# eth.net
KiCad netlist of a schematic drawn in Altium Designer
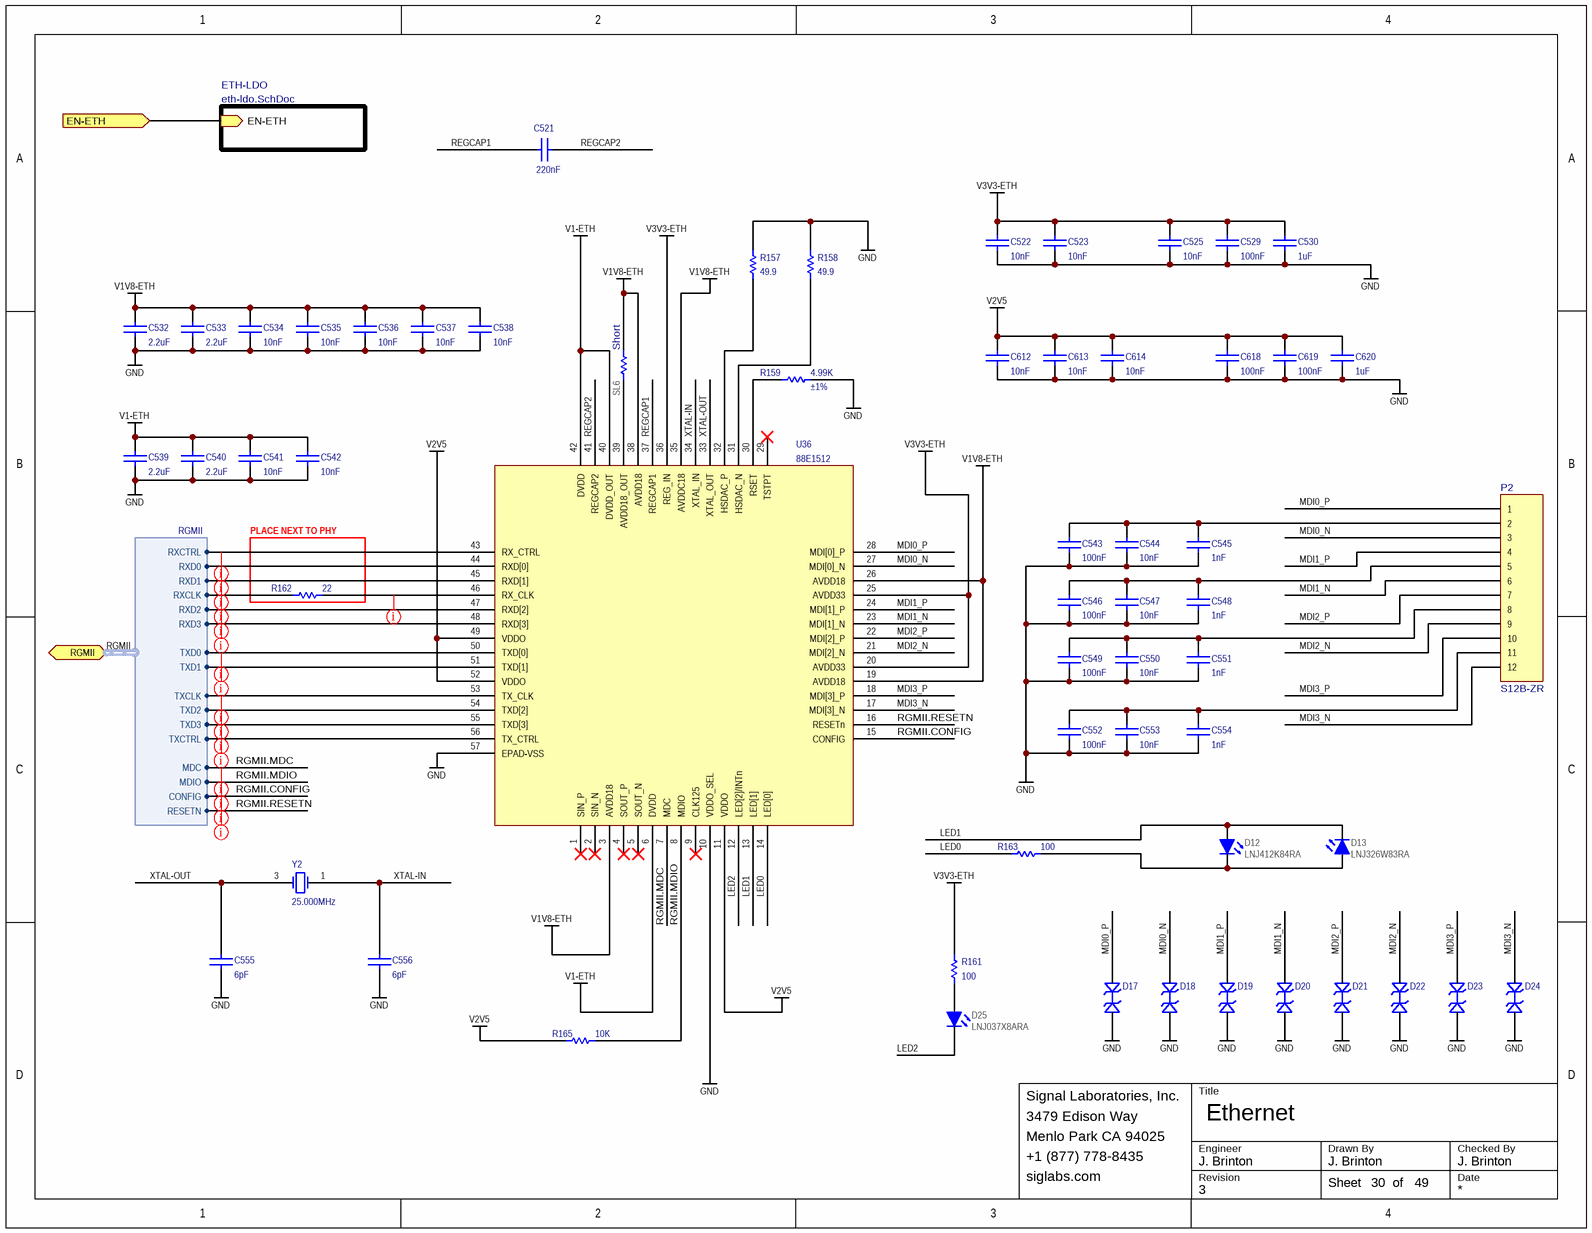
[diagram p0: eth.SchDoc]

(export (version "E")
  (design (tool "Eeschema 10.0.6"))
  (components
    (comp (ref "C521")
      (value "220nF")
      (footprint "CAPC100X50X55L25N")
      (description "Ceramic Capacitor 220nF ±10% 25V X7R 0402")
      (fields (field (name "VOLTAGE") "25V") (field (name "MANUFACTURER") "TDK"))
      (libsource (lib "Graviton") (part "CAP 0402"))
    )
    (comp (ref "C522")
      (value "10nF")
      (footprint "CAPC100X50X55L25N")
      (description "Ceramic Capacitor 10nF ±10% 50V X7R 0402")
      (fields (field (name "VOLTAGE") "50V") (field (name "MANUFACTURER") "Murata"))
      (libsource (lib "Graviton") (part "CAP 0402"))
    )
    (comp (ref "C523")
      (value "10nF")
      (footprint "CAPC100X50X55L25N")
      (description "Ceramic Capacitor 10nF ±10% 50V X7R 0402")
      (fields (field (name "VOLTAGE") "50V") (field (name "MANUFACTURER") "Murata"))
      (libsource (lib "Graviton") (part "CAP 0402"))
    )
    (comp (ref "C525")
      (value "10nF")
      (footprint "CAPC100X50X55L25N")
      (description "Ceramic Capacitor 10nF ±10% 50V X7R 0402")
      (fields (field (name "VOLTAGE") "50V") (field (name "MANUFACTURER") "Murata"))
      (libsource (lib "Graviton") (part "CAP 0402"))
    )
    (comp (ref "C529")
      (value "100nF")
      (footprint "CAPC100X50X55L25N")
      (description "Ceramic Capacitor 100nF ±10% 16V X7R 0402")
      (fields (field (name "VOLTAGE") "16V") (field (name "MANUFACTURER") "Murata"))
      (libsource (lib "Graviton") (part "CAP 0402"))
    )
    (comp (ref "C530")
      (value "1uF")
      (footprint "CAPC100X50X55L25N")
      (description "Ceramic Capacitor 1uF ±10% 10V X5R 0402")
      (fields (field (name "VOLTAGE") "10V") (field (name "MANUFACTURER") "Murata"))
      (libsource (lib "Graviton") (part "CAP 0402"))
    )
    (comp (ref "C532")
      (value "2.2uF")
      (footprint "CAPC160X80X90L20N")
      (description "Ceramic Capacitor 2.2uF ±10% 10V X7R 0603")
      (fields (field (name "VOLTAGE") "10V") (field (name "MANUFACTURER") "Murata"))
      (libsource (lib "Graviton") (part "CAP 0805"))
    )
    (comp (ref "C533")
      (value "2.2uF")
      (footprint "CAPC160X80X90L20N")
      (description "Ceramic Capacitor 2.2uF ±10% 10V X7R 0603")
      (fields (field (name "VOLTAGE") "10V") (field (name "MANUFACTURER") "Murata"))
      (libsource (lib "Graviton") (part "CAP 0805"))
    )
    (comp (ref "C534")
      (value "10nF")
      (footprint "CAPC100X50X55L25N")
      (description "Ceramic Capacitor 10nF ±10% 50V X7R 0402")
      (fields (field (name "VOLTAGE") "50V") (field (name "MANUFACTURER") "Murata"))
      (libsource (lib "Graviton") (part "CAP 0402"))
    )
    (comp (ref "C535")
      (value "10nF")
      (footprint "CAPC100X50X55L25N")
      (description "Ceramic Capacitor 10nF ±10% 50V X7R 0402")
      (fields (field (name "VOLTAGE") "50V") (field (name "MANUFACTURER") "Murata"))
      (libsource (lib "Graviton") (part "CAP 0402"))
    )
    (comp (ref "C536")
      (value "10nF")
      (footprint "CAPC100X50X55L25N")
      (description "Ceramic Capacitor 10nF ±10% 50V X7R 0402")
      (fields (field (name "VOLTAGE") "50V") (field (name "MANUFACTURER") "Murata"))
      (libsource (lib "Graviton") (part "CAP 0402"))
    )
    (comp (ref "C537")
      (value "10nF")
      (footprint "CAPC100X50X55L25N")
      (description "Ceramic Capacitor 10nF ±10% 50V X7R 0402")
      (fields (field (name "VOLTAGE") "50V") (field (name "MANUFACTURER") "Murata"))
      (libsource (lib "Graviton") (part "CAP 0402"))
    )
    (comp (ref "C538")
      (value "10nF")
      (footprint "CAPC100X50X55L25N")
      (description "Ceramic Capacitor 10nF ±10% 50V X7R 0402")
      (fields (field (name "VOLTAGE") "50V") (field (name "MANUFACTURER") "Murata"))
      (libsource (lib "Graviton") (part "CAP 0402"))
    )
    (comp (ref "C539")
      (value "2.2uF")
      (footprint "CAPC160X80X90L20N")
      (description "Ceramic Capacitor 2.2uF ±10% 10V X7R 0603")
      (fields (field (name "VOLTAGE") "10V") (field (name "MANUFACTURER") "Murata"))
      (libsource (lib "Graviton") (part "CAP 0805"))
    )
    (comp (ref "C540")
      (value "2.2uF")
      (footprint "CAPC160X80X90L20N")
      (description "Ceramic Capacitor 2.2uF ±10% 10V X7R 0603")
      (fields (field (name "VOLTAGE") "10V") (field (name "MANUFACTURER") "Murata"))
      (libsource (lib "Graviton") (part "CAP 0805"))
    )
    (comp (ref "C541")
      (value "10nF")
      (footprint "CAPC100X50X55L25N")
      (description "Ceramic Capacitor 10nF ±10% 50V X7R 0402")
      (fields (field (name "VOLTAGE") "50V") (field (name "MANUFACTURER") "Murata"))
      (libsource (lib "Graviton") (part "CAP 0402"))
    )
    (comp (ref "C542")
      (value "10nF")
      (footprint "CAPC100X50X55L25N")
      (description "Ceramic Capacitor 10nF ±10% 50V X7R 0402")
      (fields (field (name "VOLTAGE") "50V") (field (name "MANUFACTURER") "Murata"))
      (libsource (lib "Graviton") (part "CAP 0402"))
    )
    (comp (ref "C543")
      (value "100nF")
      (footprint "CAPC100X50X55L25N")
      (description "Ceramic Capacitor 100nF ±10% 16V X7R 0402")
      (fields (field (name "VOLTAGE") "16V") (field (name "MANUFACTURER") "Murata"))
      (libsource (lib "Graviton") (part "CAP 0402"))
    )
    (comp (ref "C544")
      (value "10nF")
      (footprint "CAPC100X50X55L25N")
      (description "Ceramic Capacitor 10nF ±10% 50V X7R 0402")
      (fields (field (name "VOLTAGE") "50V") (field (name "MANUFACTURER") "Murata"))
      (libsource (lib "Graviton") (part "CAP 0402"))
    )
    (comp (ref "C545")
      (value "1nF")
      (footprint "CAPC100X50X55L25N")
      (description "Ceramic Capacitor 1nF ±5% 50V NP0 0402")
      (fields (field (name "VOLTAGE") "50V") (field (name "MANUFACTURER") "TDK"))
      (libsource (lib "Graviton") (part "CAP 0402"))
    )
    (comp (ref "C546")
      (value "100nF")
      (footprint "CAPC100X50X55L25N")
      (description "Ceramic Capacitor 100nF ±10% 16V X7R 0402")
      (fields (field (name "VOLTAGE") "16V") (field (name "MANUFACTURER") "Murata"))
      (libsource (lib "Graviton") (part "CAP 0402"))
    )
    (comp (ref "C547")
      (value "10nF")
      (footprint "CAPC100X50X55L25N")
      (description "Ceramic Capacitor 10nF ±10% 50V X7R 0402")
      (fields (field (name "VOLTAGE") "50V") (field (name "MANUFACTURER") "Murata"))
      (libsource (lib "Graviton") (part "CAP 0402"))
    )
    (comp (ref "C548")
      (value "1nF")
      (footprint "CAPC100X50X55L25N")
      (description "Ceramic Capacitor 1nF ±5% 50V NP0 0402")
      (fields (field (name "VOLTAGE") "50V") (field (name "MANUFACTURER") "TDK"))
      (libsource (lib "Graviton") (part "CAP 0402"))
    )
    (comp (ref "C549")
      (value "100nF")
      (footprint "CAPC100X50X55L25N")
      (description "Ceramic Capacitor 100nF ±10% 16V X7R 0402")
      (fields (field (name "VOLTAGE") "16V") (field (name "MANUFACTURER") "Murata"))
      (libsource (lib "Graviton") (part "CAP 0402"))
    )
    (comp (ref "C550")
      (value "10nF")
      (footprint "CAPC100X50X55L25N")
      (description "Ceramic Capacitor 10nF ±10% 50V X7R 0402")
      (fields (field (name "VOLTAGE") "50V") (field (name "MANUFACTURER") "Murata"))
      (libsource (lib "Graviton") (part "CAP 0402"))
    )
    (comp (ref "C551")
      (value "1nF")
      (footprint "CAPC100X50X55L25N")
      (description "Ceramic Capacitor 1nF ±5% 50V NP0 0402")
      (fields (field (name "VOLTAGE") "50V") (field (name "MANUFACTURER") "TDK"))
      (libsource (lib "Graviton") (part "CAP 0402"))
    )
    (comp (ref "C552")
      (value "100nF")
      (footprint "CAPC100X50X55L25N")
      (description "Ceramic Capacitor 100nF ±10% 16V X7R 0402")
      (fields (field (name "VOLTAGE") "16V") (field (name "MANUFACTURER") "Murata"))
      (libsource (lib "Graviton") (part "CAP 0402"))
    )
    (comp (ref "C553")
      (value "10nF")
      (footprint "CAPC100X50X55L25N")
      (description "Ceramic Capacitor 10nF ±10% 50V X7R 0402")
      (fields (field (name "VOLTAGE") "50V") (field (name "MANUFACTURER") "Murata"))
      (libsource (lib "Graviton") (part "CAP 0402"))
    )
    (comp (ref "C554")
      (value "1nF")
      (footprint "CAPC100X50X55L25N")
      (description "Ceramic Capacitor 1nF ±5% 50V NP0 0402")
      (fields (field (name "VOLTAGE") "50V") (field (name "MANUFACTURER") "TDK"))
      (libsource (lib "Graviton") (part "CAP 0402"))
    )
    (comp (ref "C555")
      (value "6pF")
      (footprint "CAPC100X50X55L25N")
      (description "Ceramic Capacitor 6pF ±0.25pF 50V NP0 RF 0402")
      (fields (field (name "VOLTAGE") "50V") (field (name "MANUFACTURER") "Murata"))
      (libsource (lib "Graviton") (part "CAP 0402"))
    )
    (comp (ref "C556")
      (value "6pF")
      (footprint "CAPC100X50X55L25N")
      (description "Ceramic Capacitor 6pF ±0.25pF 50V NP0 RF 0402")
      (fields (field (name "VOLTAGE") "50V") (field (name "MANUFACTURER") "Murata"))
      (libsource (lib "Graviton") (part "CAP 0402"))
    )
    (comp (ref "C612")
      (value "10nF")
      (footprint "CAPC100X50X55L25N")
      (description "Ceramic Capacitor 10nF ±10% 50V X7R 0402")
      (fields (field (name "VOLTAGE") "50V") (field (name "MANUFACTURER") "Murata"))
      (libsource (lib "Graviton") (part "CAP 0402"))
    )
    (comp (ref "C613")
      (value "10nF")
      (footprint "CAPC100X50X55L25N")
      (description "Ceramic Capacitor 10nF ±10% 50V X7R 0402")
      (fields (field (name "VOLTAGE") "50V") (field (name "MANUFACTURER") "Murata"))
      (libsource (lib "Graviton") (part "CAP 0402"))
    )
    (comp (ref "C614")
      (value "10nF")
      (footprint "CAPC100X50X55L25N")
      (description "Ceramic Capacitor 10nF ±10% 50V X7R 0402")
      (fields (field (name "VOLTAGE") "50V") (field (name "MANUFACTURER") "Murata"))
      (libsource (lib "Graviton") (part "CAP 0402"))
    )
    (comp (ref "C618")
      (value "100nF")
      (footprint "CAPC100X50X55L25N")
      (description "Ceramic Capacitor 100nF ±10% 16V X7R 0402")
      (fields (field (name "VOLTAGE") "16V") (field (name "MANUFACTURER") "Murata"))
      (libsource (lib "Graviton") (part "CAP 0402"))
    )
    (comp (ref "C619")
      (value "100nF")
      (footprint "CAPC100X50X55L25N")
      (description "Ceramic Capacitor 100nF ±10% 16V X7R 0402")
      (fields (field (name "VOLTAGE") "16V") (field (name "MANUFACTURER") "Murata"))
      (libsource (lib "Graviton") (part "CAP 0402"))
    )
    (comp (ref "C620")
      (value "1uF")
      (footprint "CAPC100X50X55L25N")
      (description "Ceramic Capacitor 1uF ±10% 10V X5R 0402")
      (fields (field (name "VOLTAGE") "10V") (field (name "MANUFACTURER") "Murata"))
      (libsource (lib "Graviton") (part "CAP 0402"))
    )
    (comp (ref "D12")
      (value "LNJ412K84RA")
      (footprint "0603_LED")
      (description "LED, SMT 0603, Color Amber, 10mA, 2.05V")
      (fields (field (name "MANUFACTURER") "Panasonic"))
      (libsource (lib "generic") (part "LED0603Y"))
    )
    (comp (ref "D13")
      (value "LNJ326W83RA")
      (footprint "0603_LED")
      (description "LED, SMT 0603, Color Green, 10mA, 2.05V")
      (fields (field (name "MANUFACTURER") "Panasonic"))
      (libsource (lib "generic") (part "LED0603GR"))
    )
    (comp (ref "D17")
      (value "ESD8472")
      (footprint "XFDFN-2")
      (description "ESD Protection Diode")
      (fields (field (name "MANUFACTURER") "On Semiconductor"))
      (libsource (lib "on_semi") (part "ESD8472"))
    )
    (comp (ref "D18")
      (value "ESD8472")
      (footprint "XFDFN-2")
      (description "ESD Protection Diode")
      (fields (field (name "MANUFACTURER") "On Semiconductor"))
      (libsource (lib "on_semi") (part "ESD8472"))
    )
    (comp (ref "D19")
      (value "ESD8472")
      (footprint "XFDFN-2")
      (description "ESD Protection Diode")
      (fields (field (name "MANUFACTURER") "On Semiconductor"))
      (libsource (lib "on_semi") (part "ESD8472"))
    )
    (comp (ref "D20")
      (value "ESD8472")
      (footprint "XFDFN-2")
      (description "ESD Protection Diode")
      (fields (field (name "MANUFACTURER") "On Semiconductor"))
      (libsource (lib "on_semi") (part "ESD8472"))
    )
    (comp (ref "D21")
      (value "ESD8472")
      (footprint "XFDFN-2")
      (description "ESD Protection Diode")
      (fields (field (name "MANUFACTURER") "On Semiconductor"))
      (libsource (lib "on_semi") (part "ESD8472"))
    )
    (comp (ref "D22")
      (value "ESD8472")
      (footprint "XFDFN-2")
      (description "ESD Protection Diode")
      (fields (field (name "MANUFACTURER") "On Semiconductor"))
      (libsource (lib "on_semi") (part "ESD8472"))
    )
    (comp (ref "D23")
      (value "ESD8472")
      (footprint "XFDFN-2")
      (description "ESD Protection Diode")
      (fields (field (name "MANUFACTURER") "On Semiconductor"))
      (libsource (lib "on_semi") (part "ESD8472"))
    )
    (comp (ref "D24")
      (value "ESD8472")
      (footprint "XFDFN-2")
      (description "ESD Protection Diode")
      (fields (field (name "MANUFACTURER") "On Semiconductor"))
      (libsource (lib "on_semi") (part "ESD8472"))
    )
    (comp (ref "D25")
      (value "LNJ037X8ARA")
      (footprint "0603_LED")
      (description "LED, SMT 0603, Color White, 10mA, 2.05V")
      (fields (field (name "MANUFACTURER") "Panasonic"))
      (libsource (lib "generic") (part "LED0603GR"))
    )
    (comp (ref "P2")
      (value "S12B-ZR")
      (footprint "jst:S12B-ZR")
      (description "1.5mm pitch right angle 12-position")
      (fields (field (name "MANUFACTURER") "JST"))
      (libsource (lib "jst") (part "S12B-ZR"))
    )
    (comp (ref "R157")
      (value "49.9")
      (footprint "RESC1005X40N")
      (description "Thin Film Resistor 49.9 ±0.1% 0402")
      (fields (field (name "MANUFACTURER") "Panasonic") (field (name "TOLERANCE") "±0.1%"))
      (libsource (lib "Graviton") (part "RES 0402"))
    )
    (comp (ref "R158")
      (value "49.9")
      (footprint "RESC1005X40N")
      (description "Thin Film Resistor 49.9 ±0.1% 0402")
      (fields (field (name "MANUFACTURER") "Panasonic") (field (name "TOLERANCE") "±0.1%"))
      (libsource (lib "Graviton") (part "RES 0402"))
    )
    (comp (ref "R159")
      (value "4.99K")
      (footprint "RESC1005X40N")
      (description "Thick Film Resistor 4.99k ±1% 0402")
      (fields
        (field (name "MANUFACTURER") "Panasonic")
        (field (name "TOLERANCE") "±1%")
        (field (name "Comment") "ERJ-2RKF4991X")
      )
      (libsource (lib "Graviton") (part "RES 0402"))
    )
    (comp (ref "R161")
      (value "100")
      (footprint "RESC1005X40N")
      (description "Thin Film Resistor 100 ±0.1% 0402")
      (fields (field (name "MANUFACTURER") "Panasonic") (field (name "TOLERANCE") "±0.1%"))
      (libsource (lib "Graviton") (part "RES 0402"))
    )
    (comp (ref "R162")
      (value "22")
      (footprint "RESC1005X40N")
      (description "Thick Film Resistor 22 ±1% 0402")
      (fields (field (name "MANUFACTURER") "Yageo") (field (name "TOLERANCE") "±1%"))
      (libsource (lib "Graviton") (part "RES 0402"))
    )
    (comp (ref "R163")
      (value "100")
      (footprint "RESC1005X40N")
      (description "Thin Film Resistor 100 ±0.1% 0402")
      (fields (field (name "MANUFACTURER") "Panasonic") (field (name "TOLERANCE") "±0.1%"))
      (libsource (lib "Graviton") (part "RES 0402"))
    )
    (comp (ref "R165")
      (value "10K")
      (footprint "RESC1005X40N")
      (description "Thick Film Resistor 10k ±1% 0.1W 50V 0402")
      (fields (field (name "MANUFACTURER") "Panasonic") (field (name "TOLERANCE") "±1%"))
      (libsource (lib "Graviton") (part "RES 0402"))
    )
    (comp (ref "SL6")
      (value "SOLDER_LINK")
      (footprint "SOLDERLINK0603X26N_BRIDGED")
      (description "Solder Link, Bridged")
      (fields (field (name "NOTES") "Short"))
      (libsource (lib "generic") (part "RES"))
    )
    (comp (ref "U36")
      (value "88E1512")
      (footprint "QFN-56")
      (description "Alaska Intergrated 1000/100/10 Ethernet PHY")
      (fields (field (name "MANUFACTURER") "Marvell"))
      (libsource (lib "marvell") (part "88E1512"))
    )
    (comp (ref "Y2")
      (value "XRCGB25M000F3N00R0")
      (footprint "XRCGB")
      (description "CRYSTAL, 25.000MHz, 30ppm, 6pF")
      (fields (field (name "MANUFACTURER") "Murata") (field (name "FREQ") "25.000MHz"))
      (libsource (lib "murata") (part "XRCGB25M000F3N00R0"))
    )
  )
  (nets
    (net (code "3") (name "/LED0") (class "Default")
      (node (ref "R163") (pin "1") (pinfunction "1_1") (pintype "passive"))
      (node (ref "U36") (pin "14") (pinfunction "LED[0]_14") (pintype "passive"))
    )
    (net (code "4") (name "/LED1") (class "Default")
      (node (ref "D12") (pin "1") (pinfunction "A_1") (pintype "passive"))
      (node (ref "D13") (pin "2") (pinfunction "K_2") (pintype "passive"))
      (node (ref "U36") (pin "13") (pinfunction "LED[1]_13") (pintype "passive"))
    )
    (net (code "5") (name "/LED2") (class "Default")
      (node (ref "D25") (pin "2") (pinfunction "K_2") (pintype "passive"))
      (node (ref "U36") (pin "12") (pinfunction "LED[2]/INTn_12") (pintype "passive"))
    )
    (net (code "6") (name "/MDI0_N") (class "Default")
      (node (ref "D18") (pin "1") (pinfunction "1_1") (pintype "passive"))
      (node (ref "P2") (pin "3") (pinfunction "3_3") (pintype "passive"))
      (node (ref "U36") (pin "27") (pinfunction "MDI[0]_N_27") (pintype "passive"))
    )
    (net (code "7") (name "/MDI0_P") (class "Default")
      (node (ref "D17") (pin "1") (pinfunction "1_1") (pintype "passive"))
      (node (ref "P2") (pin "1") (pinfunction "1_1") (pintype "passive"))
      (node (ref "U36") (pin "28") (pinfunction "MDI[0]_P_28") (pintype "passive"))
    )
    (net (code "8") (name "/MDI1_N") (class "Default")
      (node (ref "D20") (pin "1") (pinfunction "1_1") (pintype "passive"))
      (node (ref "P2") (pin "6") (pinfunction "6_6") (pintype "passive"))
      (node (ref "U36") (pin "23") (pinfunction "MDI[1]_N_23") (pintype "passive"))
    )
    (net (code "9") (name "/MDI1_P") (class "Default")
      (node (ref "D19") (pin "1") (pinfunction "1_1") (pintype "passive"))
      (node (ref "P2") (pin "4") (pinfunction "4_4") (pintype "passive"))
      (node (ref "U36") (pin "24") (pinfunction "MDI[1]_P_24") (pintype "passive"))
    )
    (net (code "10") (name "/MDI2_N") (class "Default")
      (node (ref "D22") (pin "1") (pinfunction "1_1") (pintype "passive"))
      (node (ref "P2") (pin "9") (pinfunction "9_9") (pintype "passive"))
      (node (ref "U36") (pin "21") (pinfunction "MDI[2]_N_21") (pintype "passive"))
    )
    (net (code "11") (name "/MDI2_P") (class "Default")
      (node (ref "D21") (pin "1") (pinfunction "1_1") (pintype "passive"))
      (node (ref "P2") (pin "7") (pinfunction "7_7") (pintype "passive"))
      (node (ref "U36") (pin "22") (pinfunction "MDI[2]_P_22") (pintype "passive"))
    )
    (net (code "12") (name "/MDI3_N") (class "Default")
      (node (ref "D24") (pin "1") (pinfunction "1_1") (pintype "passive"))
      (node (ref "P2") (pin "12") (pinfunction "12_12") (pintype "passive"))
      (node (ref "U36") (pin "17") (pinfunction "MDI[3]_N_17") (pintype "passive"))
    )
    (net (code "13") (name "/MDI3_P") (class "Default")
      (node (ref "D23") (pin "1") (pinfunction "1_1") (pintype "passive"))
      (node (ref "P2") (pin "10") (pinfunction "10_10") (pintype "passive"))
      (node (ref "U36") (pin "18") (pinfunction "MDI[3]_P_18") (pintype "passive"))
    )
    (net (code "14") (name "/REGCAP1") (class "Default")
      (node (ref "C521") (pin "1") (pinfunction "1_1") (pintype "passive"))
      (node (ref "U36") (pin "37") (pinfunction "REGCAP1_37") (pintype "passive"))
    )
    (net (code "15") (name "/REGCAP2") (class "Default")
      (node (ref "C521") (pin "2") (pinfunction "2_2") (pintype "passive"))
      (node (ref "U36") (pin "41") (pinfunction "REGCAP2_41") (pintype "passive"))
    )
    (net (code "16") (name "/RGMII.CONFIG") (class "Default")
      (node (ref "U36") (pin "15") (pinfunction "CONFIG_15") (pintype "passive"))
    )
    (net (code "17") (name "/RGMII.MDC") (class "Default")
      (node (ref "U36") (pin "7") (pinfunction "MDC_7") (pintype "passive"))
    )
    (net (code "18") (name "/RGMII.MDIO") (class "Default")
      (node (ref "R165") (pin "1") (pinfunction "1_1") (pintype "passive"))
      (node (ref "U36") (pin "8") (pinfunction "MDIO_8") (pintype "passive"))
    )
    (net (code "19") (name "/RGMII.RESETN") (class "Default")
      (node (ref "U36") (pin "16") (pinfunction "RESETn_16") (pintype "passive"))
    )
    (net (code "21") (name "/RXCLK") (class "Default")
      (node (ref "R162") (pin "1") (pinfunction "1_1") (pintype "passive"))
    )
    (net (code "22") (name "/RXCTRL") (class "Default")
      (node (ref "U36") (pin "43") (pinfunction "RX_CTRL_43") (pintype "passive"))
    )
    (net (code "23") (name "/RXD0") (class "Default")
      (node (ref "U36") (pin "44") (pinfunction "RXD[0]_44") (pintype "passive"))
    )
    (net (code "24") (name "/RXD1") (class "Default")
      (node (ref "U36") (pin "45") (pinfunction "RXD[1]_45") (pintype "passive"))
    )
    (net (code "25") (name "/RXD2") (class "Default")
      (node (ref "U36") (pin "47") (pinfunction "RXD[2]_47") (pintype "passive"))
    )
    (net (code "26") (name "/RXD3") (class "Default")
      (node (ref "U36") (pin "48") (pinfunction "RXD[3]_48") (pintype "passive"))
    )
    (net (code "27") (name "/TXCLK") (class "Default")
      (node (ref "U36") (pin "53") (pinfunction "TX_CLK_53") (pintype "passive"))
    )
    (net (code "28") (name "/TXCTRL") (class "Default")
      (node (ref "U36") (pin "56") (pinfunction "TX_CTRL_56") (pintype "passive"))
    )
    (net (code "29") (name "/TXD0") (class "Default")
      (node (ref "U36") (pin "50") (pinfunction "TXD[0]_50") (pintype "passive"))
    )
    (net (code "30") (name "/TXD1") (class "Default")
      (node (ref "U36") (pin "51") (pinfunction "TXD[1]_51") (pintype "passive"))
    )
    (net (code "31") (name "/TXD2") (class "Default")
      (node (ref "U36") (pin "54") (pinfunction "TXD[2]_54") (pintype "passive"))
    )
    (net (code "32") (name "/TXD3") (class "Default")
      (node (ref "U36") (pin "55") (pinfunction "TXD[3]_55") (pintype "passive"))
    )
    (net (code "33") (name "/XTAL-IN") (class "Default")
      (node (ref "C556") (pin "2") (pinfunction "2_2") (pintype "passive"))
      (node (ref "U36") (pin "34") (pinfunction "XTAL_IN_34") (pintype "passive"))
      (node (ref "Y2") (pin "1") (pinfunction "OSC1_1") (pintype "passive"))
    )
    (net (code "34") (name "/XTAL-OUT") (class "Default")
      (node (ref "C555") (pin "2") (pinfunction "2_2") (pintype "passive"))
      (node (ref "U36") (pin "33") (pinfunction "XTAL_OUT_33") (pintype "passive"))
      (node (ref "Y2") (pin "3") (pinfunction "OSC2_3") (pintype "passive"))
    )
    (net (code "35") (name "GND") (class "Default")
      (node (ref "C522") (pin "1") (pinfunction "1_1") (pintype "passive"))
      (node (ref "C523") (pin "1") (pinfunction "1_1") (pintype "passive"))
      (node (ref "C525") (pin "1") (pinfunction "1_1") (pintype "passive"))
      (node (ref "C529") (pin "1") (pinfunction "1_1") (pintype "passive"))
      (node (ref "C530") (pin "1") (pinfunction "1_1") (pintype "passive"))
      (node (ref "C532") (pin "1") (pinfunction "1_1") (pintype "passive"))
      (node (ref "C533") (pin "1") (pinfunction "1_1") (pintype "passive"))
      (node (ref "C534") (pin "1") (pinfunction "1_1") (pintype "passive"))
      (node (ref "C535") (pin "1") (pinfunction "1_1") (pintype "passive"))
      (node (ref "C536") (pin "1") (pinfunction "1_1") (pintype "passive"))
      (node (ref "C537") (pin "1") (pinfunction "1_1") (pintype "passive"))
      (node (ref "C538") (pin "1") (pinfunction "1_1") (pintype "passive"))
      (node (ref "C539") (pin "1") (pinfunction "1_1") (pintype "passive"))
      (node (ref "C540") (pin "1") (pinfunction "1_1") (pintype "passive"))
      (node (ref "C541") (pin "1") (pinfunction "1_1") (pintype "passive"))
      (node (ref "C542") (pin "1") (pinfunction "1_1") (pintype "passive"))
      (node (ref "C543") (pin "1") (pinfunction "1_1") (pintype "passive"))
      (node (ref "C544") (pin "1") (pinfunction "1_1") (pintype "passive"))
      (node (ref "C545") (pin "1") (pinfunction "1_1") (pintype "passive"))
      (node (ref "C546") (pin "1") (pinfunction "1_1") (pintype "passive"))
      (node (ref "C547") (pin "1") (pinfunction "1_1") (pintype "passive"))
      (node (ref "C548") (pin "1") (pinfunction "1_1") (pintype "passive"))
      (node (ref "C549") (pin "1") (pinfunction "1_1") (pintype "passive"))
      (node (ref "C550") (pin "1") (pinfunction "1_1") (pintype "passive"))
      (node (ref "C551") (pin "1") (pinfunction "1_1") (pintype "passive"))
      (node (ref "C552") (pin "1") (pinfunction "1_1") (pintype "passive"))
      (node (ref "C553") (pin "1") (pinfunction "1_1") (pintype "passive"))
      (node (ref "C554") (pin "1") (pinfunction "1_1") (pintype "passive"))
      (node (ref "C555") (pin "1") (pinfunction "1_1") (pintype "passive"))
      (node (ref "C556") (pin "1") (pinfunction "1_1") (pintype "passive"))
      (node (ref "C612") (pin "1") (pinfunction "1_1") (pintype "passive"))
      (node (ref "C613") (pin "1") (pinfunction "1_1") (pintype "passive"))
      (node (ref "C614") (pin "1") (pinfunction "1_1") (pintype "passive"))
      (node (ref "C618") (pin "1") (pinfunction "1_1") (pintype "passive"))
      (node (ref "C619") (pin "1") (pinfunction "1_1") (pintype "passive"))
      (node (ref "C620") (pin "1") (pinfunction "1_1") (pintype "passive"))
      (node (ref "D17") (pin "2") (pinfunction "2_2") (pintype "passive"))
      (node (ref "D18") (pin "2") (pinfunction "2_2") (pintype "passive"))
      (node (ref "D19") (pin "2") (pinfunction "2_2") (pintype "passive"))
      (node (ref "D20") (pin "2") (pinfunction "2_2") (pintype "passive"))
      (node (ref "D21") (pin "2") (pinfunction "2_2") (pintype "passive"))
      (node (ref "D22") (pin "2") (pinfunction "2_2") (pintype "passive"))
      (node (ref "D23") (pin "2") (pinfunction "2_2") (pintype "passive"))
      (node (ref "D24") (pin "2") (pinfunction "2_2") (pintype "passive"))
      (node (ref "R157") (pin "1") (pinfunction "1_1") (pintype "passive"))
      (node (ref "R158") (pin "1") (pinfunction "1_1") (pintype "passive"))
      (node (ref "R159") (pin "1") (pinfunction "1_1") (pintype "passive"))
      (node (ref "U36") (pin "10") (pinfunction "VDDO_SEL_10") (pintype "passive"))
      (node (ref "U36") (pin "57") (pinfunction "EPAD-VSS_57") (pintype "passive"))
    )
    (net (code "36") (name "Net-(C543-Pad2)") (class "Default")
      (node (ref "C543") (pin "2") (pinfunction "2_2") (pintype "passive"))
      (node (ref "C544") (pin "2") (pinfunction "2_2") (pintype "passive"))
      (node (ref "C545") (pin "2") (pinfunction "2_2") (pintype "passive"))
      (node (ref "P2") (pin "2") (pinfunction "2_2") (pintype "passive"))
    )
    (net (code "37") (name "Net-(C546-Pad2)") (class "Default")
      (node (ref "C546") (pin "2") (pinfunction "2_2") (pintype "passive"))
      (node (ref "C547") (pin "2") (pinfunction "2_2") (pintype "passive"))
      (node (ref "C548") (pin "2") (pinfunction "2_2") (pintype "passive"))
      (node (ref "P2") (pin "5") (pinfunction "5_5") (pintype "passive"))
    )
    (net (code "38") (name "Net-(C549-Pad2)") (class "Default")
      (node (ref "C549") (pin "2") (pinfunction "2_2") (pintype "passive"))
      (node (ref "C550") (pin "2") (pinfunction "2_2") (pintype "passive"))
      (node (ref "C551") (pin "2") (pinfunction "2_2") (pintype "passive"))
      (node (ref "P2") (pin "8") (pinfunction "8_8") (pintype "passive"))
    )
    (net (code "39") (name "Net-(C552-Pad2)") (class "Default")
      (node (ref "C552") (pin "2") (pinfunction "2_2") (pintype "passive"))
      (node (ref "C553") (pin "2") (pinfunction "2_2") (pintype "passive"))
      (node (ref "C554") (pin "2") (pinfunction "2_2") (pintype "passive"))
      (node (ref "P2") (pin "11") (pinfunction "11_11") (pintype "passive"))
    )
    (net (code "40") (name "Net-(D12-K)") (class "Default")
      (node (ref "D12") (pin "2") (pinfunction "K_2") (pintype "passive"))
      (node (ref "D13") (pin "1") (pinfunction "A_1") (pintype "passive"))
      (node (ref "R163") (pin "2") (pinfunction "2_2") (pintype "passive"))
    )
    (net (code "41") (name "Net-(D25-A)") (class "Default")
      (node (ref "D25") (pin "1") (pinfunction "A_1") (pintype "passive"))
      (node (ref "R161") (pin "2") (pinfunction "2_2") (pintype "passive"))
    )
    (net (code "42") (name "Net-(U36-AVDD18_OUT)") (class "Default")
      (node (ref "SL6") (pin "2") (pinfunction "2_2") (pintype "passive"))
      (node (ref "U36") (pin "39") (pinfunction "AVDD18_OUT_39") (pintype "passive"))
    )
    (net (code "43") (name "Net-(U36-HSDAC_N)") (class "Default")
      (node (ref "R158") (pin "2") (pinfunction "2_2") (pintype "passive"))
      (node (ref "U36") (pin "31") (pinfunction "HSDAC_N_31") (pintype "passive"))
    )
    (net (code "44") (name "Net-(U36-HSDAC_P)") (class "Default")
      (node (ref "R157") (pin "2") (pinfunction "2_2") (pintype "passive"))
      (node (ref "U36") (pin "32") (pinfunction "HSDAC_P_32") (pintype "passive"))
    )
    (net (code "45") (name "Net-(U36-RSET)") (class "Default")
      (node (ref "R159") (pin "2") (pinfunction "2_2") (pintype "passive"))
      (node (ref "U36") (pin "30") (pinfunction "RSET_30") (pintype "passive"))
    )
    (net (code "46") (name "Net-(U36-RX_CLK)") (class "Default")
      (node (ref "R162") (pin "2") (pinfunction "2_2") (pintype "passive"))
      (node (ref "U36") (pin "46") (pinfunction "RX_CLK_46") (pintype "passive"))
    )
    (net (code "47") (name "V1-ETH") (class "Default")
      (node (ref "C539") (pin "2") (pinfunction "2_2") (pintype "passive"))
      (node (ref "C540") (pin "2") (pinfunction "2_2") (pintype "passive"))
      (node (ref "C541") (pin "2") (pinfunction "2_2") (pintype "passive"))
      (node (ref "C542") (pin "2") (pinfunction "2_2") (pintype "passive"))
      (node (ref "U36") (pin "40") (pinfunction "DVDD_OUT_40") (pintype "passive"))
      (node (ref "U36") (pin "42") (pinfunction "DVDD_42") (pintype "passive"))
      (node (ref "U36") (pin "6") (pinfunction "DVDD_6") (pintype "passive"))
    )
    (net (code "48") (name "V1V8-ETH") (class "Default")
      (node (ref "C532") (pin "2") (pinfunction "2_2") (pintype "passive"))
      (node (ref "C533") (pin "2") (pinfunction "2_2") (pintype "passive"))
      (node (ref "C534") (pin "2") (pinfunction "2_2") (pintype "passive"))
      (node (ref "C535") (pin "2") (pinfunction "2_2") (pintype "passive"))
      (node (ref "C536") (pin "2") (pinfunction "2_2") (pintype "passive"))
      (node (ref "C537") (pin "2") (pinfunction "2_2") (pintype "passive"))
      (node (ref "C538") (pin "2") (pinfunction "2_2") (pintype "passive"))
      (node (ref "SL6") (pin "1") (pinfunction "1_1") (pintype "passive"))
      (node (ref "U36") (pin "19") (pinfunction "AVDD18_19") (pintype "passive"))
      (node (ref "U36") (pin "26") (pinfunction "AVDD18_26") (pintype "passive"))
      (node (ref "U36") (pin "3") (pinfunction "AVDD18_3") (pintype "passive"))
      (node (ref "U36") (pin "35") (pinfunction "AVDDC18_35") (pintype "passive"))
      (node (ref "U36") (pin "38") (pinfunction "AVDD18_38") (pintype "passive"))
    )
    (net (code "49") (name "V2V5") (class "Default")
      (node (ref "C612") (pin "2") (pinfunction "2_2") (pintype "passive"))
      (node (ref "C613") (pin "2") (pinfunction "2_2") (pintype "passive"))
      (node (ref "C614") (pin "2") (pinfunction "2_2") (pintype "passive"))
      (node (ref "C618") (pin "2") (pinfunction "2_2") (pintype "passive"))
      (node (ref "C619") (pin "2") (pinfunction "2_2") (pintype "passive"))
      (node (ref "C620") (pin "2") (pinfunction "2_2") (pintype "passive"))
      (node (ref "R165") (pin "2") (pinfunction "2_2") (pintype "passive"))
      (node (ref "U36") (pin "11") (pinfunction "VDDO_11") (pintype "passive"))
      (node (ref "U36") (pin "49") (pinfunction "VDDO_49") (pintype "passive"))
      (node (ref "U36") (pin "52") (pinfunction "VDDO_52") (pintype "passive"))
    )
    (net (code "50") (name "V3V3-ETH") (class "Default")
      (node (ref "C522") (pin "2") (pinfunction "2_2") (pintype "passive"))
      (node (ref "C523") (pin "2") (pinfunction "2_2") (pintype "passive"))
      (node (ref "C525") (pin "2") (pinfunction "2_2") (pintype "passive"))
      (node (ref "C529") (pin "2") (pinfunction "2_2") (pintype "passive"))
      (node (ref "C530") (pin "2") (pinfunction "2_2") (pintype "passive"))
      (node (ref "R161") (pin "1") (pinfunction "1_1") (pintype "passive"))
      (node (ref "U36") (pin "20") (pinfunction "AVDD33_20") (pintype "passive"))
      (node (ref "U36") (pin "25") (pinfunction "AVDD33_25") (pintype "passive"))
      (node (ref "U36") (pin "36") (pinfunction "REG_IN_36") (pintype "passive"))
    )
    (net (code "51") (name "unconnected-(U36-CLK125-Pad9)") (class "Default")
      (node (ref "U36") (pin "9") (pinfunction "CLK125_9") (pintype "passive+no_connect"))
    )
    (net (code "52") (name "unconnected-(U36-SIN_N-Pad2)") (class "Default")
      (node (ref "U36") (pin "2") (pinfunction "SIN_N_2") (pintype "passive+no_connect"))
    )
    (net (code "53") (name "unconnected-(U36-SIN_P-Pad1)") (class "Default")
      (node (ref "U36") (pin "1") (pinfunction "SIN_P_1") (pintype "passive+no_connect"))
    )
    (net (code "54") (name "unconnected-(U36-SOUT_N-Pad5)") (class "Default")
      (node (ref "U36") (pin "5") (pinfunction "SOUT_N_5") (pintype "passive+no_connect"))
    )
    (net (code "55") (name "unconnected-(U36-SOUT_P-Pad4)") (class "Default")
      (node (ref "U36") (pin "4") (pinfunction "SOUT_P_4") (pintype "passive+no_connect"))
    )
    (net (code "56") (name "unconnected-(U36-TSTPT-Pad29)") (class "Default")
      (node (ref "U36") (pin "29") (pinfunction "TSTPT_29") (pintype "passive+no_connect"))
    )
    (net (code "57") (name "unconnected-(Y2-NC-Pad2)") (class "Default")
      (node (ref "Y2") (pin "2") (pinfunction "NC_2") (pintype "passive"))
    )
    (net (code "58") (name "unconnected-(Y2-NC-Pad4)") (class "Default")
      (node (ref "Y2") (pin "4") (pinfunction "NC_4") (pintype "passive"))
    )
  )
)
